# ControllerWaveyRadar.net
KiCad netlist of a schematic drawn in Altium Designer
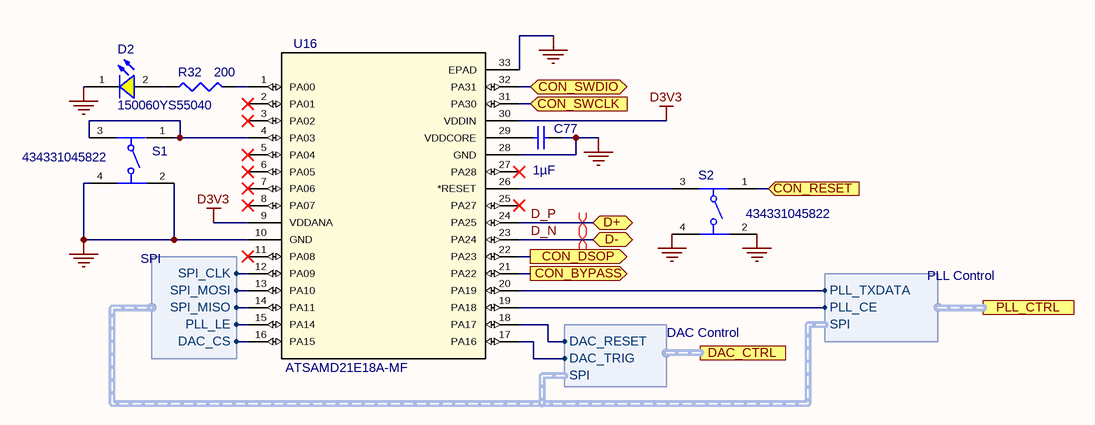
[diagram p0: ControllerWaveyRadar.SchDoc]

(export (version "E")
  (design (tool "Eeschema 10.0.6"))
  (components
    (comp (ref "C77")
      (value "1µF")
      (footprint "CAPC0402(1005)60_L")
      (description "Chip Capacitor, 1µF +/-20%, 10V, 0402, Thickness 0.6 mm")
      (fields (field (name "TOLERANCE") "10%") (field (name "Comment") "Capacitor 1µF +/-20% 10V 0402"))
      (libsource (lib "University of South Florida") (part "CAP-NP-2"))
    )
    (comp (ref "D2")
      (value "150060YS55040")
      (footprint "WL-SMCD_0603")
      (description "WL-SMCD SMT Mono-color Chip LED Diffused, size 0603, Yellow, 2V, 140deg")
      (fields (field (name "PUBLISHER") "Wurth Elektronik"))
      (libsource (lib "University of South Florida") (part "150060YS55040"))
    )
    (comp (ref "R32")
      (value "200")
      (footprint "RESC0402(1005)_L")
      (description "Chip Resistor, 200 Ohms, +/-5 %, 63 mW, -55 to 155 degC, 0402")
      (fields (field (name "POWER") "63mW") (field (name "TOLERANCE") "5%"))
      (libsource (lib "University of South Florida") (part "RES-2"))
    )
    (comp (ref "S1")
      (value "434331045822")
      (footprint "434331045822")
      (description "WS-TASU SMT Tact Switch 4.7x3.5mm side push, height 1.65mm, 220gf")
      (fields (field (name "MANUFACTURER") "Wurth Elektronik"))
      (libsource (lib "University of South Florida") (part "434331045822"))
    )
    (comp (ref "S2")
      (value "434331045822")
      (footprint "434331045822")
      (description "WS-TASU SMT Tact Switch 4.7x3.5mm side push, height 1.65mm, 220gf")
      (fields (field (name "MANUFACTURER") "Wurth Elektronik"))
      (libsource (lib "University of South Florida") (part "434331045822"))
    )
    (comp (ref "U16")
      (value "ATSAMD21E18A-MF")
      (footprint "QFN32_5X5MC_MCH")
      (description "No Description Available")
      (fields (field (name "COPYRIGHT") "Copyright (C) 2018 Accelerated Designs. All rights reserved"))
      (libsource (lib "University of South Florida") (part "ATSAMD21E18A-MF"))
    )
  )
  (nets
    (net (code "5") (name "/CON_BYPASS") (class "Default")
      (node (ref "U16") (pin "21") (pinfunction "PA22_21") (pintype "bidirectional"))
    )
    (net (code "6") (name "/CON_DSOP") (class "Default")
      (node (ref "U16") (pin "22") (pinfunction "PA23_22") (pintype "bidirectional"))
    )
    (net (code "7") (name "/CON_RESET") (class "Default")
      (node (ref "S2") (pin "1") (pinfunction "1_1") (pintype "passive"))
    )
    (net (code "8") (name "/CON_SWCLK") (class "Default")
      (node (ref "U16") (pin "31") (pinfunction "PA30_31") (pintype "bidirectional"))
    )
    (net (code "9") (name "/CON_SWDIO") (class "Default")
      (node (ref "U16") (pin "32") (pinfunction "PA31_32") (pintype "bidirectional"))
    )
    (net (code "10") (name "/DAC_CS") (class "Default")
      (node (ref "U16") (pin "16") (pinfunction "PA15_16") (pintype "bidirectional"))
    )
    (net (code "11") (name "/DAC_RESET") (class "Default")
      (node (ref "U16") (pin "18") (pinfunction "PA17_18") (pintype "bidirectional"))
    )
    (net (code "12") (name "/DAC_TRIG") (class "Default")
      (node (ref "U16") (pin "17") (pinfunction "PA16_17") (pintype "bidirectional"))
    )
    (net (code "13") (name "/D_N") (class "Default")
      (node (ref "U16") (pin "23") (pinfunction "PA24_23") (pintype "bidirectional"))
    )
    (net (code "14") (name "/D_P") (class "Default")
      (node (ref "U16") (pin "24") (pinfunction "PA25_24") (pintype "bidirectional"))
    )
    (net (code "15") (name "/PLL_CE") (class "Default")
      (node (ref "U16") (pin "19") (pinfunction "PA18_19") (pintype "bidirectional"))
    )
    (net (code "16") (name "/PLL_LE") (class "Default")
      (node (ref "U16") (pin "15") (pinfunction "PA14_15") (pintype "bidirectional"))
    )
    (net (code "17") (name "/PLL_TXDATA") (class "Default")
      (node (ref "U16") (pin "20") (pinfunction "PA19_20") (pintype "bidirectional"))
    )
    (net (code "18") (name "/SPI_CLK") (class "Default")
      (node (ref "U16") (pin "12") (pinfunction "PA09_12") (pintype "bidirectional"))
    )
    (net (code "19") (name "/SPI_MISO") (class "Default")
      (node (ref "U16") (pin "14") (pinfunction "PA11_14") (pintype "bidirectional"))
    )
    (net (code "20") (name "/SPI_MOSI") (class "Default")
      (node (ref "U16") (pin "13") (pinfunction "PA10_13") (pintype "bidirectional"))
    )
    (net (code "24") (name "D3V3") (class "Default")
      (node (ref "U16") (pin "30") (pinfunction "VDDIN_30") (pintype "power_in"))
      (node (ref "U16") (pin "9") (pinfunction "VDDANA_9") (pintype "power_in"))
    )
    (net (code "25") (name "GND") (class "Default")
      (node (ref "C77") (pin "2") (pinfunction "2_2") (pintype "passive"))
      (node (ref "D2") (pin "1") (pinfunction "K_1") (pintype "passive"))
      (node (ref "S1") (pin "2") (pinfunction "2_2") (pintype "passive"))
      (node (ref "S1") (pin "4") (pinfunction "4_4") (pintype "passive"))
      (node (ref "S2") (pin "2") (pinfunction "2_2") (pintype "passive"))
      (node (ref "S2") (pin "4") (pinfunction "4_4") (pintype "passive"))
      (node (ref "U16") (pin "10") (pinfunction "GND_10") (pintype "passive"))
      (node (ref "U16") (pin "28") (pinfunction "GND_28") (pintype "passive"))
      (node (ref "U16") (pin "33") (pinfunction "EPAD_33") (pintype "passive"))
    )
    (net (code "26") (name "Net-(D2-A)") (class "Default")
      (node (ref "D2") (pin "2") (pinfunction "A_2") (pintype "passive"))
      (node (ref "R32") (pin "1") (pinfunction "1_1") (pintype "passive"))
    )
    (net (code "27") (name "Net-(U16-*RESET)") (class "Default")
      (node (ref "S2") (pin "3") (pinfunction "3_3") (pintype "passive"))
      (node (ref "U16") (pin "26") (pinfunction "*RESET_26") (pintype "passive"))
    )
    (net (code "28") (name "Net-(U16-PA00)") (class "Default")
      (node (ref "R32") (pin "2") (pinfunction "2_2") (pintype "passive"))
      (node (ref "U16") (pin "1") (pinfunction "PA00_1") (pintype "bidirectional"))
    )
    (net (code "29") (name "Net-(U16-PA03)") (class "Default")
      (node (ref "S1") (pin "1") (pinfunction "1_1") (pintype "passive"))
      (node (ref "S1") (pin "3") (pinfunction "3_3") (pintype "passive"))
      (node (ref "U16") (pin "4") (pinfunction "PA03_4") (pintype "bidirectional"))
    )
    (net (code "30") (name "Net-(U16-VDDCORE)") (class "Default")
      (node (ref "C77") (pin "1") (pinfunction "1_1") (pintype "passive"))
      (node (ref "U16") (pin "29") (pinfunction "VDDCORE_29") (pintype "power_in"))
    )
    (net (code "31") (name "unconnected-(U16-PA01-Pad2)") (class "Default")
      (node (ref "U16") (pin "2") (pinfunction "PA01_2") (pintype "bidirectional+no_connect"))
    )
    (net (code "32") (name "unconnected-(U16-PA02-Pad3)") (class "Default")
      (node (ref "U16") (pin "3") (pinfunction "PA02_3") (pintype "bidirectional+no_connect"))
    )
    (net (code "33") (name "unconnected-(U16-PA04-Pad5)") (class "Default")
      (node (ref "U16") (pin "5") (pinfunction "PA04_5") (pintype "bidirectional+no_connect"))
    )
    (net (code "34") (name "unconnected-(U16-PA05-Pad6)") (class "Default")
      (node (ref "U16") (pin "6") (pinfunction "PA05_6") (pintype "bidirectional+no_connect"))
    )
    (net (code "35") (name "unconnected-(U16-PA06-Pad7)") (class "Default")
      (node (ref "U16") (pin "7") (pinfunction "PA06_7") (pintype "bidirectional+no_connect"))
    )
    (net (code "36") (name "unconnected-(U16-PA07-Pad8)") (class "Default")
      (node (ref "U16") (pin "8") (pinfunction "PA07_8") (pintype "bidirectional+no_connect"))
    )
    (net (code "37") (name "unconnected-(U16-PA08-Pad11)") (class "Default")
      (node (ref "U16") (pin "11") (pinfunction "PA08_11") (pintype "bidirectional+no_connect"))
    )
    (net (code "38") (name "unconnected-(U16-PA27-Pad25)") (class "Default")
      (node (ref "U16") (pin "25") (pinfunction "PA27_25") (pintype "bidirectional+no_connect"))
    )
    (net (code "39") (name "unconnected-(U16-PA28-Pad27)") (class "Default")
      (node (ref "U16") (pin "27") (pinfunction "PA28_27") (pintype "bidirectional+no_connect"))
    )
  )
)
